# 1_Power.net
KiCad netlist of a schematic drawn in Altium Designer
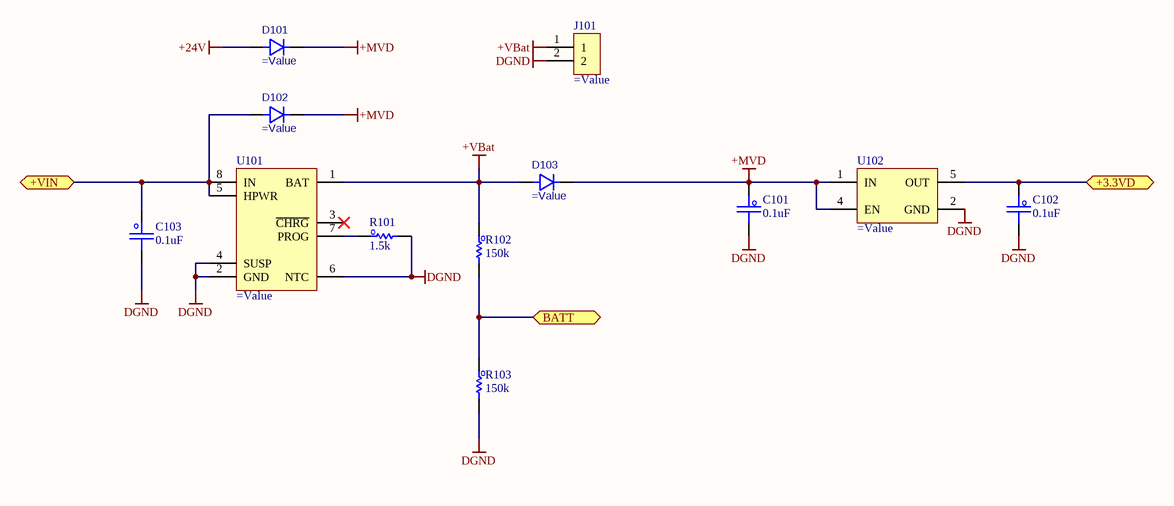
[diagram p0: 1_Power.SchDoc]

(export (version "E")
  (design (tool "Eeschema 10.0.6"))
  (components
    (comp (ref "C101")
      (value "0.1uF")
      (footprint "C_0603")
      (description "CAP CER 0.1UF 50V X7R 0603")
      (fields (field (name "MANUFACTURER") "KEMET") (field (name "PARTNUMBER") "C0603C104K5RACTU"))
      (libsource (lib "UUSymbol") (part "C_Capacitor"))
    )
    (comp (ref "C102")
      (value "0.1uF")
      (footprint "C_0603")
      (description "CAP CER 0.1UF 50V X7R 0603")
      (fields (field (name "MANUFACTURER") "KEMET") (field (name "PARTNUMBER") "C0603C104K5RACTU"))
      (libsource (lib "UUSymbol") (part "C_Capacitor"))
    )
    (comp (ref "C103")
      (value "0.1uF")
      (footprint "C_0603")
      (description "CAP CER 0.1UF 50V X7R 0603")
      (fields (field (name "MANUFACTURER") "KEMET") (field (name "PARTNUMBER") "C0603C104K5RACTU"))
      (libsource (lib "UUSymbol") (part "C_Capacitor"))
    )
    (comp (ref "D101")
      (value "~")
      (footprint "SOD323")
      (description "DIODE SCHOTTKY 40V 2A 0603")
      (fields (field (name "MANUFACTURER") "Slkor(SLKORMICRO Elec.)") (field (name "PARTNUMBER") "SD103AWS"))
      (libsource (lib "UUSymbol") (part "D_PW_SD103AWS"))
    )
    (comp (ref "D102")
      (value "~")
      (footprint "SOD323")
      (description "DIODE SCHOTTKY 40V 2A 0603")
      (fields (field (name "MANUFACTURER") "Slkor(SLKORMICRO Elec.)") (field (name "PARTNUMBER") "SD103AWS"))
      (libsource (lib "UUSymbol") (part "D_PW_SD103AWS"))
    )
    (comp (ref "D103")
      (value "~")
      (footprint "SOD323")
      (description "DIODE SCHOTTKY 40V 2A 0603")
      (fields (field (name "MANUFACTURER") "Slkor(SLKORMICRO Elec.)") (field (name "PARTNUMBER") "SD103AWS"))
      (libsource (lib "UUSymbol") (part "D_PW_SD103AWS"))
    )
    (comp (ref "J101")
      (value "~")
      (footprint "CON_2P_Header")
      (description "Connector 2 position")
      (fields
        (field (name "PARTNUMBER") "796866-2")
        (field (name "MANUFACTURER") "TE Connectivity AMP Connectors")
      )
      (libsource (lib "UUSymbol") (part "CON_2P_Heder"))
    )
    (comp (ref "R101")
      (value "1.5k")
      (footprint "R_0603")
      (description "RES 1.5K OHM 5% 1/10W 0603")
      (fields (field (name "MANUFACTURER") "Vishay Dale") (field (name "PARTNUMBER") "CRCW06031K50JNEAC"))
      (libsource (lib "UUSymbol") (part "R_Resister"))
    )
    (comp (ref "R102")
      (value "150k")
      (footprint "R_0603")
      (description "RES SMD 150K OHM 1% 1/10W 0603")
      (fields (field (name "MANUFACTURER") "Vishay Dale") (field (name "PARTNUMBER") "CRCW0603150KFKEAC"))
      (libsource (lib "UUSymbol") (part "R_Resister"))
    )
    (comp (ref "R103")
      (value "150k")
      (footprint "R_0603")
      (description "RES SMD 150K OHM 1% 1/10W 0603")
      (fields (field (name "MANUFACTURER") "Vishay Dale") (field (name "PARTNUMBER") "CRCW0603150KFKEAC"))
      (libsource (lib "UUSymbol") (part "R_Resister"))
    )
    (comp (ref "U101")
      (value "~")
      (footprint "SON45P200X200X80-9N")
      (description "IC BATT CHG LI-ION 1CELL 8DFN")
      (fields
        (field (name "PARTNUMBER") "LTC4095EDC#TRMPBF")
        (field (name "MANUFACTURER") "Analog Devices Inc.")
      )
      (libsource (lib "UUSymbol") (part "IC_PMS_LTC4095"))
    )
    (comp (ref "U102")
      (value "~")
      (footprint "SOT95P280X145-5N")
      (description "200mA 360mV@(10mA) Fixed 3.3V~3.3V Positive 1 36V SOT-23-5 Linear Voltage Regulators (LDO) ROHS")
      (fields (field (name "PARTNUMBER") "RT9069-33GB") (field (name "MANUFACTURER") "Richtek Tech"))
      (libsource (lib "UUSymbol") (part "IC_LDO_RT9069-33GB"))
    )
  )
  (nets
    (net (code "1") (name "+24V") (class "Default")
      (node (ref "D101") (pin "2") (pinfunction "2_2") (pintype "passive"))
    )
    (net (code "2") (name "+MVD") (class "Default")
      (node (ref "C101") (pin "1") (pinfunction "1_1") (pintype "passive"))
      (node (ref "D101") (pin "1") (pinfunction "1_1") (pintype "passive"))
      (node (ref "D102") (pin "1") (pinfunction "1_1") (pintype "passive"))
      (node (ref "D103") (pin "1") (pinfunction "1_1") (pintype "passive"))
      (node (ref "U102") (pin "1") (pinfunction "IN_1") (pintype "passive"))
      (node (ref "U102") (pin "4") (pinfunction "EN_4") (pintype "passive"))
    )
    (net (code "3") (name "+VBat") (class "Default")
      (node (ref "D103") (pin "2") (pinfunction "2_2") (pintype "passive"))
      (node (ref "J101") (pin "1") (pinfunction "1_1") (pintype "passive"))
      (node (ref "R102") (pin "1") (pinfunction "1_1") (pintype "passive"))
      (node (ref "U101") (pin "1") (pinfunction "BAT_1") (pintype "passive"))
    )
    (net (code "4") (name "/+3.3VD") (class "Default")
      (node (ref "C102") (pin "1") (pinfunction "1_1") (pintype "passive"))
      (node (ref "U102") (pin "5") (pinfunction "OUT_5") (pintype "passive"))
    )
    (net (code "5") (name "/+VIN") (class "Default")
      (node (ref "C103") (pin "1") (pinfunction "1_1") (pintype "passive"))
      (node (ref "D102") (pin "2") (pinfunction "2_2") (pintype "passive"))
      (node (ref "U101") (pin "5") (pinfunction "HPWR_5") (pintype "passive"))
      (node (ref "U101") (pin "8") (pinfunction "IN_8") (pintype "passive"))
    )
    (net (code "6") (name "/BATT") (class "Default")
      (node (ref "R102") (pin "2") (pinfunction "2_2") (pintype "passive"))
      (node (ref "R103") (pin "1") (pinfunction "1_1") (pintype "passive"))
    )
    (net (code "7") (name "DGND") (class "Default")
      (node (ref "C101") (pin "2") (pinfunction "2_2") (pintype "passive"))
      (node (ref "C102") (pin "2") (pinfunction "2_2") (pintype "passive"))
      (node (ref "C103") (pin "2") (pinfunction "2_2") (pintype "passive"))
      (node (ref "J101") (pin "2") (pinfunction "2_2") (pintype "passive"))
      (node (ref "R101") (pin "2") (pinfunction "2_2") (pintype "passive"))
      (node (ref "R103") (pin "2") (pinfunction "2_2") (pintype "passive"))
      (node (ref "U101") (pin "2") (pinfunction "GND_2") (pintype "passive"))
      (node (ref "U101") (pin "4") (pinfunction "SUSP_4") (pintype "passive"))
      (node (ref "U101") (pin "6") (pinfunction "NTC_6") (pintype "passive"))
      (node (ref "U102") (pin "2") (pinfunction "GND_2") (pintype "passive"))
    )
    (net (code "8") (name "Net-(U101-PROG)") (class "Default")
      (node (ref "R101") (pin "1") (pinfunction "1_1") (pintype "passive"))
      (node (ref "U101") (pin "7") (pinfunction "PROG_7") (pintype "passive"))
    )
    (net (code "9") (name "unconnected-(U101-~{CHRG}-Pad3)") (class "Default")
      (node (ref "U101") (pin "3") (pinfunction "~{CHRG}_3") (pintype "passive+no_connect"))
    )
  )
)
